# sch-split-flap-ctl.net
KiCad netlist of a schematic drawn in Altium Designer
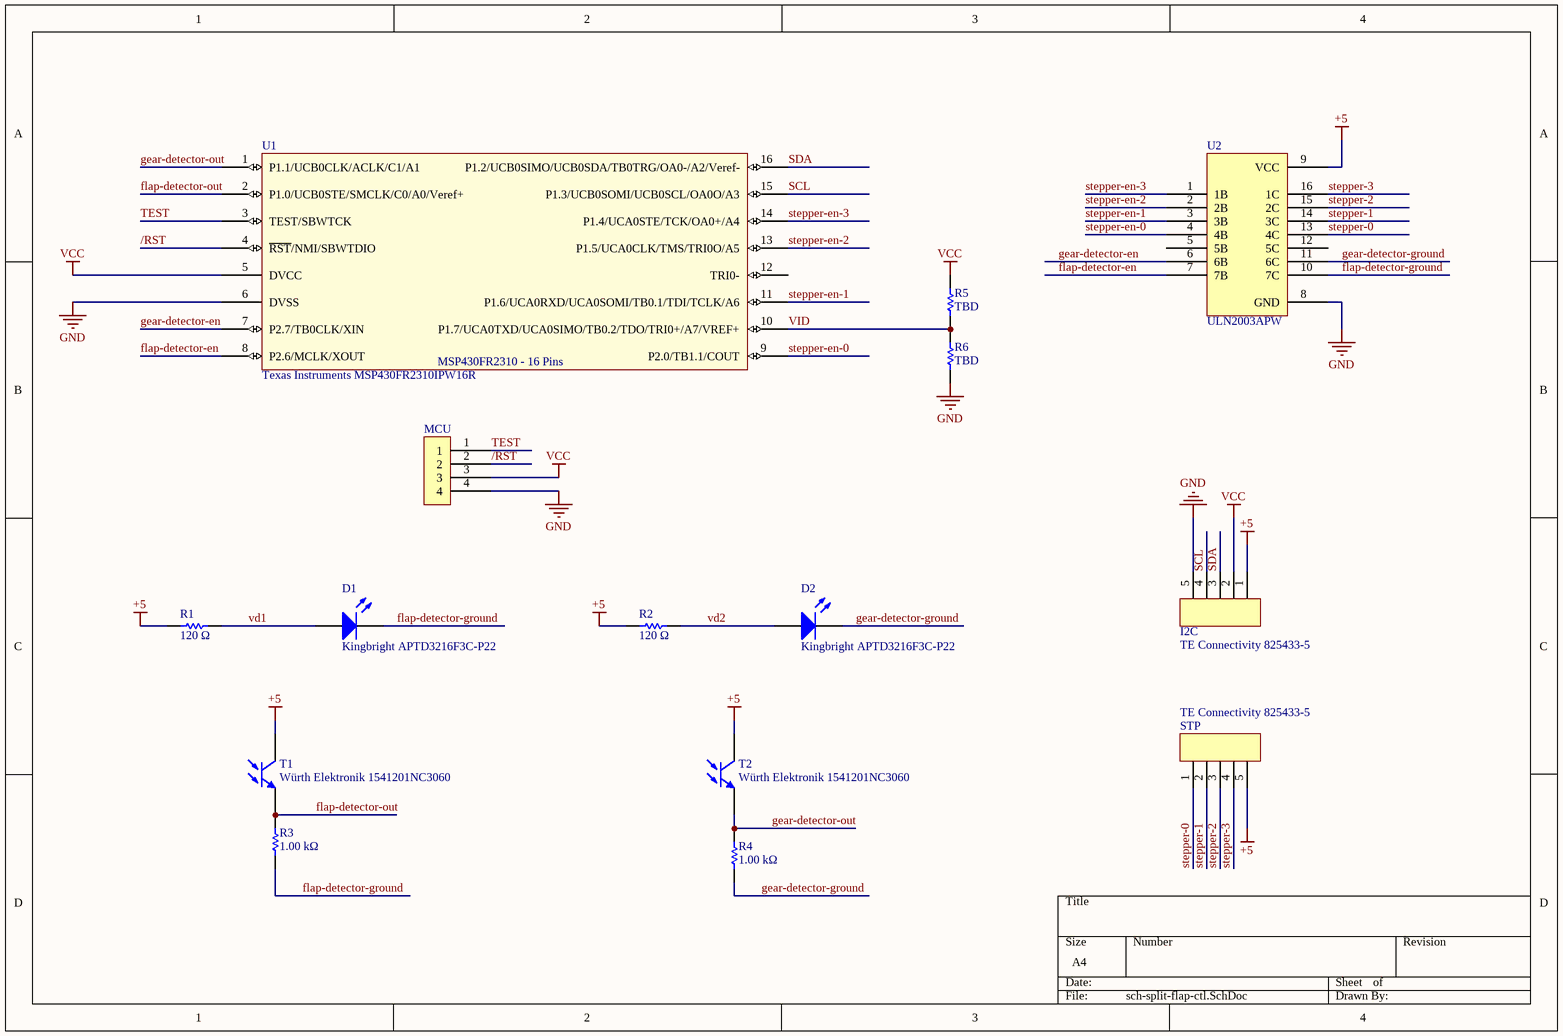
[diagram p0: sch-split-flap-ctl.SchDoc]

(export (version "E")
  (design (tool "Eeschema 10.0.6"))
  (components
    (comp (ref "D1")
      (value "Kingbright APTD3216F3C-P22")
      (footprint "PCB-jai4cqehynyl4ftrhjru-1")
      (description "Infrared Emitters 3.2x1.6mm IR SMD LED")
      (fields (field (name "MANUFACTURER PART NUMBER") "APTD3216F3C-P22"))
      (libsource (lib "FavoritesLibrary") (part "SYM-ec9320fff9353354-1"))
    )
    (comp (ref "D2")
      (value "Kingbright APTD3216F3C-P22")
      (footprint "PCB-jai4cqehynyl4ftrhjru-1")
      (description "Infrared Emitters 3.2x1.6mm IR SMD LED")
      (fields (field (name "MANUFACTURER PART NUMBER") "APTD3216F3C-P22"))
      (libsource (lib "FavoritesLibrary") (part "SYM-ec9320fff9353354-1"))
    )
    (comp (ref "I2C")
      (value "TE Connectivity 825433-5")
      (footprint "PCB-xti7u9j93a3qzo3mq4li-1")
      (description "Conn Unshrouded Header HDR 5 POS 2.54mm Solder ST Thru-Hole")
      (libsource (lib "") (part "SYM-a17c6af386817ebb-2_1"))
    )
    (comp (ref "MCU")
      (value "TE Connectivity / AMP 5-520314-4")
      (footprint "PCB-2e32bpzlb7s96t5zrzh4-1")
      (description "Wire-To-Board Connector, AMPMODU Mod II Series, Through Hole, Header, 4, 2.54 mm")
      (libsource (lib "CommunityVault") (part "CMP-5c1097d27ab083d7-7"))
    )
    (comp (ref "R1")
      (value "120 Ω")
      (footprint "PCB-2ox8asr4tk2mzt0c5jnj-1")
      (description "Surface Mount Chip Resistor, Thin Film, RT Series, 1 kohm, 100 mW, 1%, 75 V, 0603 [1608 Metric]")
      (fields (field (name "MANUFACTURER PART NUMBER") "RT0603FRE071KL"))
      (libsource (lib "FavoritesLibrary") (part "SYM-9c8b5704b0ee434c-1"))
    )
    (comp (ref "R2")
      (value "120 Ω")
      (footprint "PCB-2ox8asr4tk2mzt0c5jnj-1")
      (description "Surface Mount Chip Resistor, Thin Film, RT Series, 1 kohm, 100 mW, 1%, 75 V, 0603 [1608 Metric]")
      (fields (field (name "MANUFACTURER PART NUMBER") "RT0603FRE071KL"))
      (libsource (lib "FavoritesLibrary") (part "SYM-9c8b5704b0ee434c-1"))
    )
    (comp (ref "R3")
      (value "1.00 kΩ")
      (footprint "PCB-2ox8asr4tk2mzt0c5jnj-1")
      (description "Surface Mount Chip Resistor, Thin Film, RT Series, 1 kohm, 100 mW, 1%, 75 V, 0603 [1608 Metric]")
      (fields (field (name "MANUFACTURER PART NUMBER") "RT0603FRE071KL"))
      (libsource (lib "FavoritesLibrary") (part "SYM-9c8b5704b0ee434c-1"))
    )
    (comp (ref "R4")
      (value "1.00 kΩ")
      (footprint "PCB-2ox8asr4tk2mzt0c5jnj-1")
      (description "Surface Mount Chip Resistor, Thin Film, RT Series, 1 kohm, 100 mW, 1%, 75 V, 0603 [1608 Metric]")
      (fields (field (name "MANUFACTURER PART NUMBER") "RT0603FRE071KL"))
      (libsource (lib "FavoritesLibrary") (part "SYM-9c8b5704b0ee434c-1"))
    )
    (comp (ref "R5")
      (value "TBD")
      (footprint "PCB-2ox8asr4tk2mzt0c5jnj-1")
      (description "Surface Mount Chip Resistor, Thin Film, RT Series, 1 kohm, 100 mW, 1%, 75 V, 0603 [1608 Metric]")
      (fields (field (name "MANUFACTURER PART NUMBER") "RT0603FRE071KL"))
      (libsource (lib "FavoritesLibrary") (part "SYM-9c8b5704b0ee434c-1"))
    )
    (comp (ref "R6")
      (value "TBD")
      (footprint "PCB-2ox8asr4tk2mzt0c5jnj-1")
      (description "Surface Mount Chip Resistor, Thin Film, RT Series, 1 kohm, 100 mW, 1%, 75 V, 0603 [1608 Metric]")
      (fields (field (name "MANUFACTURER PART NUMBER") "RT0603FRE071KL"))
      (libsource (lib "FavoritesLibrary") (part "SYM-9c8b5704b0ee434c-1"))
    )
    (comp (ref "STP")
      (value "TE Connectivity 825433-5")
      (footprint "PCB-xti7u9j93a3qzo3mq4li-1")
      (description "Conn Unshrouded Header HDR 5 POS 2.54mm Solder ST Thru-Hole")
      (libsource (lib "CommunityVault") (part "SYM-a17c6af386817ebb-2"))
    )
    (comp (ref "T1")
      (value "Würth Elektronik 1541201NC3060")
      (footprint "PCB-is2cv6u2mp8dz7t5ytba-1")
      (description "Photo Transistor, NPN, 940NM, 1206")
      (libsource (lib "CommunityVault") (part "SYM-6c97a07c92ddb350-1"))
    )
    (comp (ref "T2")
      (value "Würth Elektronik 1541201NC3060")
      (footprint "PCB-is2cv6u2mp8dz7t5ytba-1")
      (description "Photo Transistor, NPN, 940NM, 1206")
      (libsource (lib "CommunityVault") (part "SYM-6c97a07c92ddb350-1"))
    )
    (comp (ref "U1")
      (value "Texas Instruments MSP430FR2310IPW16R")
      (footprint "TSSOP16")
      (fields (field (name "MANUFACTURER PART NUMBER") "MSP430FR2310IPW16R"))
      (libsource (lib "FavoritesLibrary") (part "SYM-7ebab38f542ba17d-1"))
    )
    (comp (ref "U2")
      (value "ULN2003APW")
      (footprint "PCB-o079r3vxg80uk6bdh2cv-1")
      (description "Darlington Transistor Array")
      (libsource (lib "Octopart library") (part "SYM-83444a22d3b75c83-1"))
    )
  )
  (nets
    (net (code "1") (name "+5") (class "Default")
      (node (ref "I2C") (pin "1") (pinfunction "1_1") (pintype "passive"))
      (node (ref "R1") (pin "2") (pinfunction "2_2") (pintype "passive"))
      (node (ref "R2") (pin "2") (pinfunction "2_2") (pintype "passive"))
      (node (ref "STP") (pin "5") (pinfunction "5_5") (pintype "passive"))
      (node (ref "T1") (pin "1") (pinfunction "C_1") (pintype "passive"))
      (node (ref "T2") (pin "1") (pinfunction "C_1") (pintype "passive"))
      (node (ref "U2") (pin "9") (pinfunction "VCC_9") (pintype "passive"))
    )
    (net (code "2") (name "/SCL") (class "Default")
      (node (ref "I2C") (pin "4") (pinfunction "4_4") (pintype "passive"))
      (node (ref "U1") (pin "15") (pinfunction "P1.3/UCB0SOMI/UCB0SCL/OA0O/A3_15") (pintype "bidirectional"))
    )
    (net (code "3") (name "/SDA") (class "Default")
      (node (ref "I2C") (pin "3") (pinfunction "3_3") (pintype "passive"))
      (node (ref "U1") (pin "16") (pinfunction "P1.2/UCB0SIMO/UCB0SDA/TB0TRG/OA0-/A2/Veref-_16") (pintype "bidirectional"))
    )
    (net (code "4") (name "/TEST") (class "Default")
      (node (ref "MCU") (pin "1") (pinfunction "1_1") (pintype "passive"))
      (node (ref "U1") (pin "3") (pinfunction "TEST/SBWTCK_3") (pintype "bidirectional"))
    )
    (net (code "5") (name "/VID") (class "Default")
      (node (ref "R5") (pin "1") (pinfunction "1_1") (pintype "passive"))
      (node (ref "R6") (pin "2") (pinfunction "2_2") (pintype "passive"))
      (node (ref "U1") (pin "10") (pinfunction "P1.7/UCA0TXD/UCA0SIMO/TB0.2/TDO/TRI0+/A7/VREF+_10") (pintype "bidirectional"))
    )
    (net (code "6") (name "/flap-detector-en") (class "Default")
      (node (ref "U1") (pin "8") (pinfunction "P2.6/MCLK/XOUT_8") (pintype "bidirectional"))
      (node (ref "U2") (pin "7") (pinfunction "7B_7") (pintype "passive"))
    )
    (net (code "7") (name "/flap-detector-ground") (class "Default")
      (node (ref "D1") (pin "2") (pinfunction "K_2") (pintype "passive"))
      (node (ref "R3") (pin "1") (pinfunction "1_1") (pintype "passive"))
      (node (ref "U2") (pin "10") (pinfunction "7C_10") (pintype "passive"))
    )
    (net (code "8") (name "/flap-detector-out") (class "Default")
      (node (ref "R3") (pin "2") (pinfunction "2_2") (pintype "passive"))
      (node (ref "T1") (pin "2") (pinfunction "E_2") (pintype "passive"))
      (node (ref "U1") (pin "2") (pinfunction "P1.0/UCB0STE/SMCLK/C0/A0/Veref+_2") (pintype "bidirectional"))
    )
    (net (code "9") (name "/gear-detector-en") (class "Default")
      (node (ref "U1") (pin "7") (pinfunction "P2.7/TB0CLK/XIN_7") (pintype "bidirectional"))
      (node (ref "U2") (pin "6") (pinfunction "6B_6") (pintype "passive"))
    )
    (net (code "10") (name "/gear-detector-ground") (class "Default")
      (node (ref "D2") (pin "2") (pinfunction "K_2") (pintype "passive"))
      (node (ref "R4") (pin "1") (pinfunction "1_1") (pintype "passive"))
      (node (ref "U2") (pin "11") (pinfunction "6C_11") (pintype "passive"))
    )
    (net (code "11") (name "/gear-detector-out") (class "Default")
      (node (ref "R4") (pin "2") (pinfunction "2_2") (pintype "passive"))
      (node (ref "T2") (pin "2") (pinfunction "E_2") (pintype "passive"))
      (node (ref "U1") (pin "1") (pinfunction "P1.1/UCB0CLK/ACLK/C1/A1_1") (pintype "bidirectional"))
    )
    (net (code "12") (name "/stepper-0") (class "Default")
      (node (ref "STP") (pin "1") (pinfunction "1_1") (pintype "passive"))
      (node (ref "U2") (pin "13") (pinfunction "4C_13") (pintype "passive"))
    )
    (net (code "13") (name "/stepper-1") (class "Default")
      (node (ref "STP") (pin "2") (pinfunction "2_2") (pintype "passive"))
      (node (ref "U2") (pin "14") (pinfunction "3C_14") (pintype "passive"))
    )
    (net (code "14") (name "/stepper-2") (class "Default")
      (node (ref "STP") (pin "3") (pinfunction "3_3") (pintype "passive"))
      (node (ref "U2") (pin "15") (pinfunction "2C_15") (pintype "passive"))
    )
    (net (code "15") (name "/stepper-3") (class "Default")
      (node (ref "STP") (pin "4") (pinfunction "4_4") (pintype "passive"))
      (node (ref "U2") (pin "16") (pinfunction "1C_16") (pintype "passive"))
    )
    (net (code "16") (name "/stepper-en-0") (class "Default")
      (node (ref "U1") (pin "9") (pinfunction "P2.0/TB1.1/COUT_9") (pintype "bidirectional"))
      (node (ref "U2") (pin "4") (pinfunction "4B_4") (pintype "passive"))
    )
    (net (code "17") (name "/stepper-en-1") (class "Default")
      (node (ref "U1") (pin "11") (pinfunction "P1.6/UCA0RXD/UCA0SOMI/TB0.1/TDI/TCLK/A6_11") (pintype "bidirectional"))
      (node (ref "U2") (pin "3") (pinfunction "3B_3") (pintype "passive"))
    )
    (net (code "18") (name "/stepper-en-2") (class "Default")
      (node (ref "U1") (pin "13") (pinfunction "P1.5/UCA0CLK/TMS/TRI0O/A5_13") (pintype "bidirectional"))
      (node (ref "U2") (pin "2") (pinfunction "2B_2") (pintype "passive"))
    )
    (net (code "19") (name "/stepper-en-3") (class "Default")
      (node (ref "U1") (pin "14") (pinfunction "P1.4/UCA0STE/TCK/OA0+/A4_14") (pintype "bidirectional"))
      (node (ref "U2") (pin "1") (pinfunction "1B_1") (pintype "passive"))
    )
    (net (code "20") (name "/vd1") (class "Default")
      (node (ref "D1") (pin "1") (pinfunction "A_1") (pintype "passive"))
      (node (ref "R1") (pin "1") (pinfunction "1_1") (pintype "passive"))
    )
    (net (code "21") (name "/vd2") (class "Default")
      (node (ref "D2") (pin "1") (pinfunction "A_1") (pintype "passive"))
      (node (ref "R2") (pin "1") (pinfunction "1_1") (pintype "passive"))
    )
    (net (code "22") (name "/{slash}RST") (class "Default")
      (node (ref "MCU") (pin "2") (pinfunction "2_2") (pintype "passive"))
      (node (ref "U1") (pin "4") (pinfunction "~{RST}/NMI/SBWTDIO_4") (pintype "bidirectional"))
    )
    (net (code "23") (name "GND") (class "Default")
      (node (ref "I2C") (pin "5") (pinfunction "5_5") (pintype "passive"))
      (node (ref "MCU") (pin "4") (pinfunction "4_4") (pintype "passive"))
      (node (ref "R6") (pin "1") (pinfunction "1_1") (pintype "passive"))
      (node (ref "U1") (pin "6") (pinfunction "DVSS_6") (pintype "power_in"))
      (node (ref "U2") (pin "8") (pinfunction "GND_8") (pintype "passive"))
    )
    (net (code "24") (name "VCC") (class "Default")
      (node (ref "I2C") (pin "2") (pinfunction "2_2") (pintype "passive"))
      (node (ref "MCU") (pin "3") (pinfunction "3_3") (pintype "passive"))
      (node (ref "R5") (pin "2") (pinfunction "2_2") (pintype "passive"))
      (node (ref "U1") (pin "5") (pinfunction "DVCC_5") (pintype "power_in"))
    )
    (net (code "25") (name "unconnected-(U1-TRI0--Pad12)") (class "Default")
      (node (ref "U1") (pin "12") (pinfunction "TRI0-_12") (pintype "bidirectional"))
    )
    (net (code "26") (name "unconnected-(U2-5B-Pad5)") (class "Default")
      (node (ref "U2") (pin "5") (pinfunction "5B_5") (pintype "passive"))
    )
    (net (code "27") (name "unconnected-(U2-5C-Pad12)") (class "Default")
      (node (ref "U2") (pin "12") (pinfunction "5C_12") (pintype "passive"))
    )
  )
)
